# TCAN1146_PINOUT.net
KiCad netlist of a schematic drawn in Altium Designer
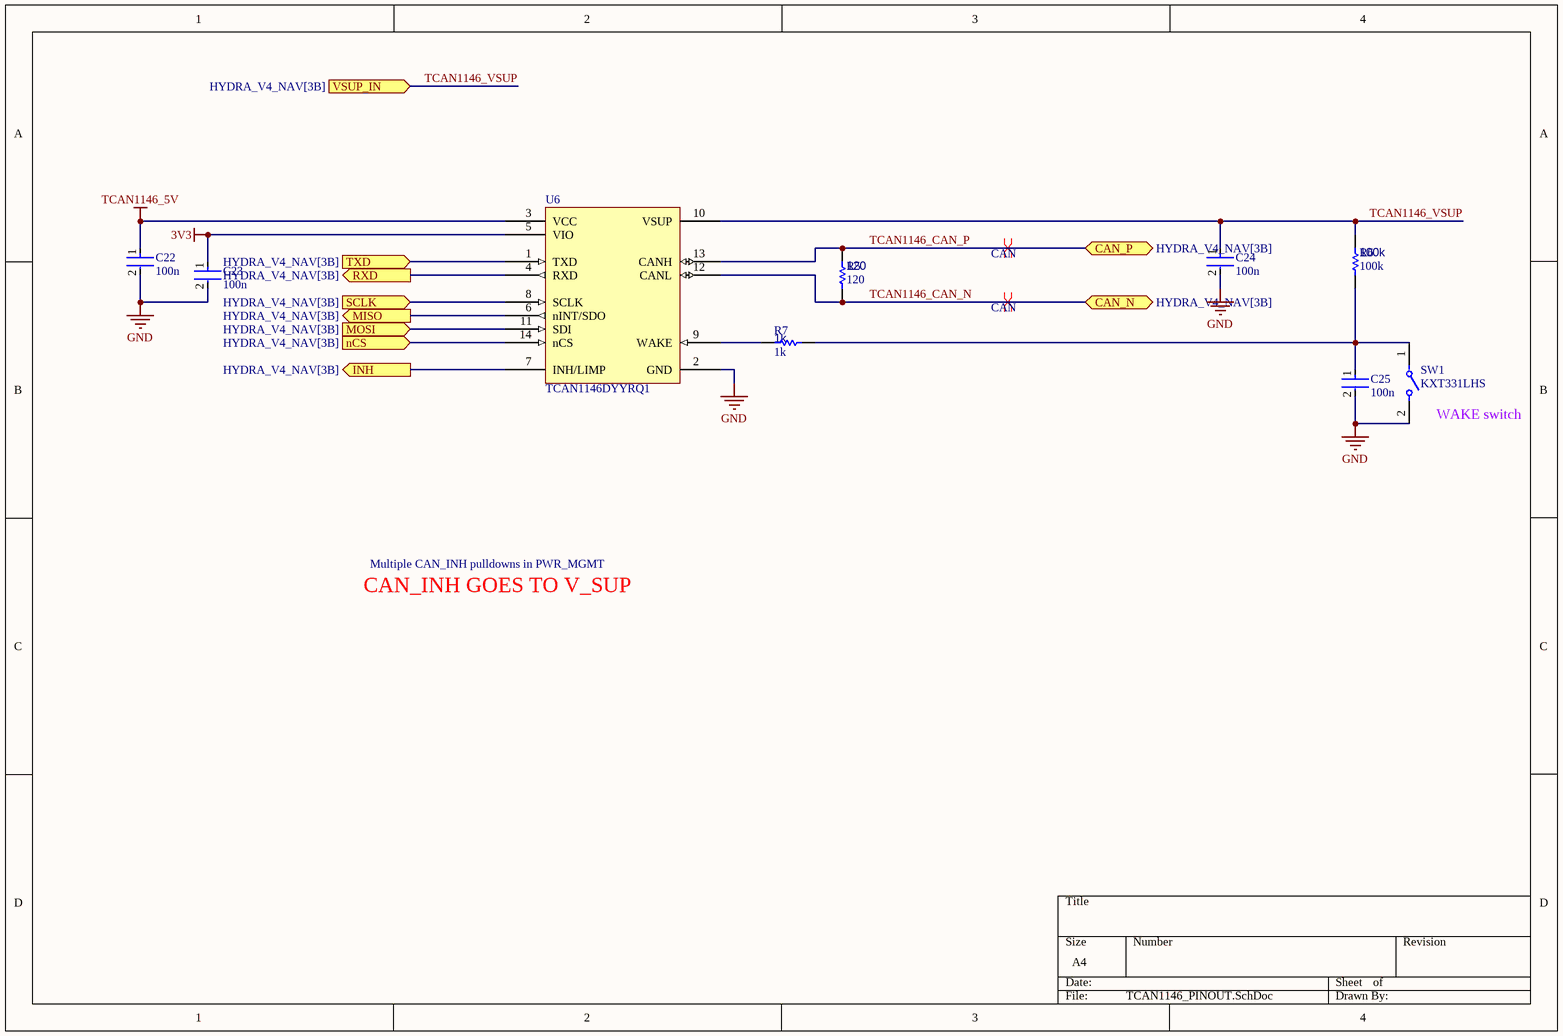
[diagram p0: TCAN1146_PINOUT.SchDoc]

(export (version "E")
  (design (tool "Eeschema 10.0.6"))
  (components
    (comp (ref "C22")
      (value "100n")
      (footprint "FP-0402-L_1_0_0_05-W_0_5-IPC_A")
      (description "LARGE PADS, 0402 CAP, CHANGE COMMENT TO MATCH REAL P/N")
      (libsource (lib "Space Concordia") (part "b4654b650e69147ec39a6b967a45e02"))
    )
    (comp (ref "C23")
      (value "100n")
      (footprint "FP-0402-L_1_0_0_05-W_0_5-IPC_A")
      (description "LARGE PADS, 0402 CAP, CHANGE COMMENT TO MATCH REAL P/N")
      (libsource (lib "Space Concordia") (part "b4654b650e69147ec39a6b967a45e02"))
    )
    (comp (ref "C24")
      (value "100n")
      (footprint "FP-0402-L_1_0_0_05-W_0_5-IPC_A")
      (description "LARGE PADS, 0402 CAP, CHANGE COMMENT TO MATCH REAL P/N")
      (libsource (lib "Space Concordia") (part "b4654b650e69147ec39a6b967a45e02"))
    )
    (comp (ref "C25")
      (value "100n")
      (footprint "FP-0402-L_1_0_0_05-W_0_5-IPC_A")
      (description "LARGE PADS, 0402 CAP, CHANGE COMMENT TO MATCH REAL P/N")
      (libsource (lib "Space Concordia") (part "b4654b650e69147ec39a6b967a45e02"))
    )
    (comp (ref "R5")
      (value "120")
      (footprint "R0603B")
      (description "Resistor")
      (fields (field (name "ALTIUM_VALUE") "120"))
      (libsource (lib "Space Concordia") (part "Resistor"))
    )
    (comp (ref "R6")
      (value "100k")
      (footprint "R0603B")
      (description "Resistor")
      (fields (field (name "ALTIUM_VALUE") "100k"))
      (libsource (lib "Space Concordia") (part "Resistor"))
    )
    (comp (ref "R7")
      (value "1k")
      (footprint "R0603B")
      (description "Resistor")
      (fields (field (name "ALTIUM_VALUE") "1k"))
      (libsource (lib "Space Concordia") (part "Resistor"))
    )
    (comp (ref "SW1")
      (value "KXT331LHS")
      (footprint "FP-KXT331LHS-MFG")
      (description "SWITCH TACTILE SPST-NO 0.02A 15V")
      (libsource (lib "Altium Content Vault") (part "bb27bde45df87f1f469753f287ef5ae"))
    )
    (comp (ref "U6")
      (value "TCAN1146DYYRQ1")
      (footprint "TCAN1146DYYRQ1-Footprint-1")
      (libsource (lib "Space Concordia") (part "CMP-015-00012-2"))
    )
  )
  (nets
    (net (code "1") (name "/INH") (class "Default")
      (node (ref "U6") (pin "7") (pinfunction "INH/LIMP_7") (pintype "passive"))
    )
    (net (code "2") (name "/MISO") (class "Default")
      (node (ref "U6") (pin "6") (pinfunction "nINT/SDO_6") (pintype "output"))
    )
    (net (code "3") (name "/MOSI") (class "Default")
      (node (ref "U6") (pin "11") (pinfunction "SDI_11") (pintype "input"))
    )
    (net (code "4") (name "/RXD") (class "Default")
      (node (ref "U6") (pin "4") (pinfunction "RXD_4") (pintype "output"))
    )
    (net (code "5") (name "/SCLK") (class "Default")
      (node (ref "U6") (pin "8") (pinfunction "SCLK_8") (pintype "input"))
    )
    (net (code "6") (name "/TCAN1146_CAN_N") (class "Default")
      (node (ref "R5") (pin "1") (pinfunction "1_1") (pintype "passive"))
      (node (ref "U6") (pin "12") (pinfunction "CANL_12") (pintype "bidirectional"))
    )
    (net (code "7") (name "/TCAN1146_CAN_P") (class "Default")
      (node (ref "R5") (pin "2") (pinfunction "2_2") (pintype "passive"))
      (node (ref "U6") (pin "13") (pinfunction "CANH_13") (pintype "bidirectional"))
    )
    (net (code "8") (name "/TCAN1146_VSUP") (class "Default")
      (node (ref "C24") (pin "1") (pinfunction "1_1") (pintype "passive"))
      (node (ref "R6") (pin "2") (pinfunction "2_2") (pintype "passive"))
      (node (ref "U6") (pin "10") (pinfunction "VSUP_10") (pintype "power_in"))
    )
    (net (code "9") (name "/TXD") (class "Default")
      (node (ref "U6") (pin "1") (pinfunction "TXD_1") (pintype "input"))
    )
    (net (code "10") (name "/nCS") (class "Default")
      (node (ref "U6") (pin "14") (pinfunction "nCS_14") (pintype "input"))
    )
    (net (code "11") (name "3V3") (class "Default")
      (node (ref "C23") (pin "1") (pinfunction "1_1") (pintype "passive"))
      (node (ref "U6") (pin "5") (pinfunction "VIO_5") (pintype "power_in"))
    )
    (net (code "12") (name "GND") (class "Default")
      (node (ref "C22") (pin "2") (pinfunction "2_2") (pintype "passive"))
      (node (ref "C23") (pin "2") (pinfunction "2_2") (pintype "passive"))
      (node (ref "C24") (pin "2") (pinfunction "2_2") (pintype "passive"))
      (node (ref "C25") (pin "2") (pinfunction "2_2") (pintype "passive"))
      (node (ref "SW1") (pin "2") (pinfunction "2_2") (pintype "passive"))
      (node (ref "U6") (pin "2") (pinfunction "GND_2") (pintype "power_in"))
    )
    (net (code "13") (name "Net-(C25-Pad1)") (class "Default")
      (node (ref "C25") (pin "1") (pinfunction "1_1") (pintype "passive"))
      (node (ref "R6") (pin "1") (pinfunction "1_1") (pintype "passive"))
      (node (ref "R7") (pin "1") (pinfunction "1_1") (pintype "passive"))
      (node (ref "SW1") (pin "1") (pinfunction "1_1") (pintype "passive"))
    )
    (net (code "14") (name "Net-(U6-WAKE)") (class "Default")
      (node (ref "R7") (pin "2") (pinfunction "2_2") (pintype "passive"))
      (node (ref "U6") (pin "9") (pinfunction "WAKE_9") (pintype "input"))
    )
    (net (code "15") (name "TCAN1146_5V") (class "Default")
      (node (ref "C22") (pin "1") (pinfunction "1_1") (pintype "passive"))
      (node (ref "U6") (pin "3") (pinfunction "VCC_3") (pintype "power_in"))
    )
  )
)
